# Adafruit_AirLift_FeatherWing.net
KiCad netlist of a schematic drawn in EAGLE
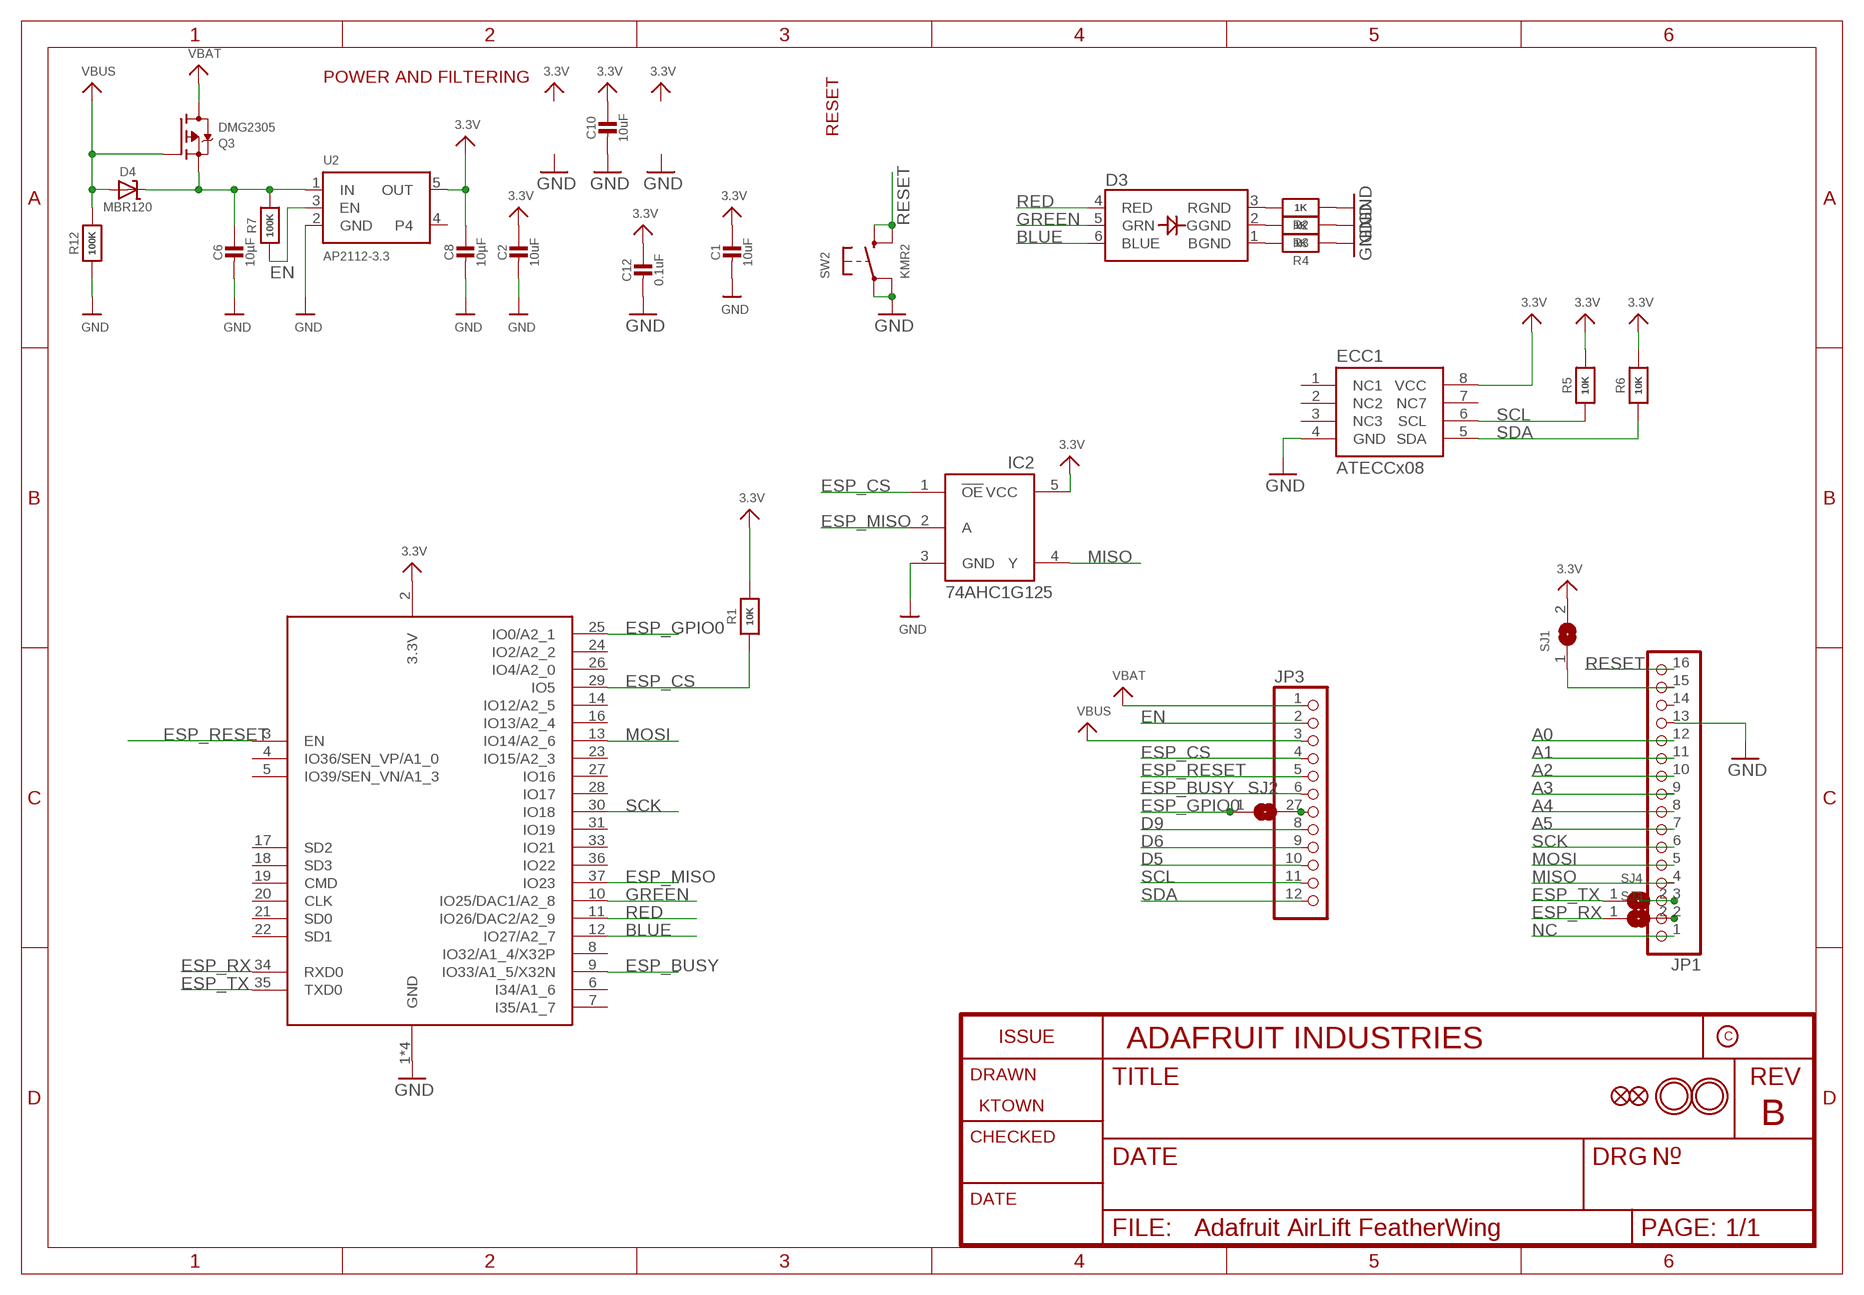
[diagram p0: schematic, sheet 1]

(export (version "E")
  (design (tool "Eeschema 10.0.6"))
  (components
    (comp (ref "C1")
      (value "10uF")
      (footprint "eagle-import:0805-NO")
      (libsource (lib "eagle-import") (part "CAP_CERAMIC0805-NOOUTLINE"))
    )
    (comp (ref "C2")
      (value "10uF")
      (footprint "eagle-import:0805-NO")
      (libsource (lib "eagle-import") (part "CAP_CERAMIC0805-NOOUTLINE"))
    )
    (comp (ref "C6")
      (value "10µF")
      (footprint "eagle-import:0805-NO")
      (libsource (lib "eagle-import") (part "CAP_CERAMIC0805-NOOUTLINE"))
    )
    (comp (ref "C8")
      (value "10µF")
      (footprint "eagle-import:0805-NO")
      (fields (field (name "REV") "B"))
      (libsource (lib "eagle-import") (part "CAP_CERAMIC0805-NOOUTLINE"))
    )
    (comp (ref "C10")
      (value "10uF")
      (footprint "eagle-import:0805-NO")
      (libsource (lib "eagle-import") (part "CAP_CERAMIC0805-NOOUTLINE"))
    )
    (comp (ref "C12")
      (value "0.1uF")
      (footprint "eagle-import:0603-NO")
      (libsource (lib "eagle-import") (part "CAP_CERAMIC0603_NO"))
    )
    (comp (ref "D3")
      (value "LED_RGB_PLCC6CREE-CLV6A")
      (footprint "eagle-import:RGBLED_PLCC6")
      (libsource (lib "eagle-import") (part "LED_RGB_PLCC6CREE-CLV6A"))
    )
    (comp (ref "D4")
      (value "MBR120")
      (footprint "eagle-import:SOD-123")
      (libsource (lib "eagle-import") (part "DIODE-SCHOTTKYSOD-123"))
    )
    (comp (ref "ECC1")
      (value "ATECCx08")
      (footprint "eagle-import:SOIC8")
      (libsource (lib "eagle-import") (part "ATECC108"))
    )
    (comp (ref "IC2")
      (value "74AHC1G125")
      (footprint "eagle-import:SOT23-5L")
      (libsource (lib "eagle-import") (part "74AHC1G125"))
    )
    (comp (ref "JP1")
      (value "HEADER-1X16_MIN")
      (footprint "eagle-import:1X16_ROUND_MIN")
      (libsource (lib "eagle-import") (part "HEADER-1X16_MIN"))
    )
    (comp (ref "JP3")
      (value "HEADER-1X12_MIN")
      (footprint "eagle-import:1X12_ROUND_MIN")
      (libsource (lib "eagle-import") (part "HEADER-1X12_MIN"))
    )
    (comp (ref "Q3")
      (value "DMG2305")
      (footprint "eagle-import:SOT23-R")
      (libsource (lib "eagle-import") (part "MOSFET-P"))
    )
    (comp (ref "R1")
      (value "10K")
      (footprint "eagle-import:0603-NO")
      (libsource (lib "eagle-import") (part "RESISTOR_0603_NOOUT"))
    )
    (comp (ref "R2")
      (value "1K")
      (footprint "eagle-import:0603-NO")
      (libsource (lib "eagle-import") (part "RESISTOR_0603_NOOUT"))
    )
    (comp (ref "R3")
      (value "1K")
      (footprint "eagle-import:0603-NO")
      (libsource (lib "eagle-import") (part "RESISTOR_0603_NOOUT"))
    )
    (comp (ref "R4")
      (value "1K")
      (footprint "eagle-import:0603-NO")
      (libsource (lib "eagle-import") (part "RESISTOR_0603_NOOUT"))
    )
    (comp (ref "R5")
      (value "10K")
      (footprint "eagle-import:0603-NO")
      (libsource (lib "eagle-import") (part "RESISTOR_0603_NOOUT"))
    )
    (comp (ref "R6")
      (value "10K")
      (footprint "eagle-import:0603-NO")
      (libsource (lib "eagle-import") (part "RESISTOR_0603_NOOUT"))
    )
    (comp (ref "R7")
      (value "100K")
      (footprint "eagle-import:0603-NO")
      (libsource (lib "eagle-import") (part "RESISTOR_0603_NOOUT"))
    )
    (comp (ref "R12")
      (value "100K")
      (footprint "eagle-import:0603-NO")
      (libsource (lib "eagle-import") (part "RESISTOR_0603_NOOUT"))
    )
    (comp (ref "SJ1")
      (value "SOLDERJUMPER")
      (footprint "eagle-import:SOLDERJUMPER_ARROW_NOPASTE")
      (libsource (lib "eagle-import") (part "SOLDERJUMPER"))
    )
    (comp (ref "SJ2")
      (value "SOLDERJUMPER")
      (footprint "eagle-import:SOLDERJUMPER_ARROW_NOPASTE")
      (libsource (lib "eagle-import") (part "SOLDERJUMPER"))
    )
    (comp (ref "SJ3")
      (value "SOLDERJUMPER")
      (footprint "eagle-import:SOLDERJUMPER_ARROW_NOPASTE")
      (libsource (lib "eagle-import") (part "SOLDERJUMPER"))
    )
    (comp (ref "SJ4")
      (value "SOLDERJUMPER")
      (footprint "eagle-import:SOLDERJUMPER_ARROW_NOPASTE")
      (libsource (lib "eagle-import") (part "SOLDERJUMPER"))
    )
    (comp (ref "SW2")
      (value "KMR2")
      (footprint "eagle-import:BTN_KMR2_4.6X2.8")
      (libsource (lib "eagle-import") (part "SWITCH_TACT_SMT4.6X2.8"))
    )
    (comp (ref "U$31")
      (value "MOUNTINGHOLE2.5")
      (footprint "eagle-import:MOUNTINGHOLE_2.5_PLATED")
      (libsource (lib "eagle-import") (part "MOUNTINGHOLE2.5"))
    )
    (comp (ref "U$32")
      (value "MOUNTINGHOLE2.5")
      (footprint "eagle-import:MOUNTINGHOLE_2.5_PLATED")
      (libsource (lib "eagle-import") (part "MOUNTINGHOLE2.5"))
    )
    (comp (ref "U$34")
      (value "FIDUCIAL_1MM")
      (footprint "eagle-import:FIDUCIAL_1MM")
      (libsource (lib "eagle-import") (part "FIDUCIAL_1MM"))
    )
    (comp (ref "U$35")
      (value "FIDUCIAL_1MM")
      (footprint "eagle-import:FIDUCIAL_1MM")
      (libsource (lib "eagle-import") (part "FIDUCIAL_1MM"))
    )
    (comp (ref "U2")
      (value "AP2112-3.3")
      (footprint "eagle-import:SOT23-5")
      (libsource (lib "eagle-import") (part "VREG_SOT23-5"))
    )
    (comp (ref "X3")
      (value "ESP32_WROOM32_SKINNY")
      (footprint "eagle-import:WROOM32_SKINNY")
      (libsource (lib "eagle-import") (part "ESP32_WROOM32_SKINNY"))
    )
  )
  (nets
    (net (code "1") (name "/A0") (class "Default")
      (node (ref "JP1") (pin "12") (pinfunction "12_12") (pintype "passive"))
    )
    (net (code "2") (name "/A1") (class "Default")
      (node (ref "JP1") (pin "11") (pinfunction "11_11") (pintype "passive"))
    )
    (net (code "3") (name "/A2") (class "Default")
      (node (ref "JP1") (pin "10") (pinfunction "10_10") (pintype "passive"))
    )
    (net (code "4") (name "/A3") (class "Default")
      (node (ref "JP1") (pin "9") (pinfunction "9_9") (pintype "passive"))
    )
    (net (code "5") (name "/A4") (class "Default")
      (node (ref "JP1") (pin "8") (pinfunction "8_8") (pintype "passive"))
    )
    (net (code "6") (name "/A5") (class "Default")
      (node (ref "JP1") (pin "7") (pinfunction "7_7") (pintype "passive"))
    )
    (net (code "7") (name "/BLUE") (class "Default")
      (node (ref "D3") (pin "6") (pinfunction "BLUE_6") (pintype "bidirectional"))
      (node (ref "X3") (pin "12") (pinfunction "IO27/A2_7_12") (pintype "bidirectional"))
    )
    (net (code "8") (name "/D5") (class "Default")
      (node (ref "JP3") (pin "10") (pinfunction "10_10") (pintype "passive"))
    )
    (net (code "9") (name "/D6") (class "Default")
      (node (ref "JP3") (pin "9") (pinfunction "9_9") (pintype "passive"))
    )
    (net (code "10") (name "/D9") (class "Default")
      (node (ref "JP3") (pin "8") (pinfunction "8_8") (pintype "passive"))
    )
    (net (code "11") (name "/EN") (class "Default")
      (node (ref "JP3") (pin "2") (pinfunction "2_2") (pintype "passive"))
      (node (ref "R7") (pin "1") (pinfunction "1_1") (pintype "passive"))
      (node (ref "U2") (pin "3") (pinfunction "EN_3") (pintype "input"))
    )
    (net (code "12") (name "/ESP_BUSY") (class "Default")
      (node (ref "JP3") (pin "6") (pinfunction "6_6") (pintype "passive"))
      (node (ref "X3") (pin "9") (pinfunction "IO33/A1_5/X32N_9") (pintype "bidirectional"))
    )
    (net (code "13") (name "/ESP_CS") (class "Default")
      (node (ref "IC2") (pin "1") (pinfunction "~{OE}_1") (pintype "input"))
      (node (ref "JP3") (pin "4") (pinfunction "4_4") (pintype "passive"))
      (node (ref "R1") (pin "1") (pinfunction "1_1") (pintype "passive"))
      (node (ref "X3") (pin "29") (pinfunction "IO5_29") (pintype "bidirectional"))
    )
    (net (code "14") (name "/ESP_GPIO0") (class "Default")
      (node (ref "SJ2") (pin "1") (pinfunction "1_1") (pintype "passive"))
      (node (ref "X3") (pin "25") (pinfunction "IO0/A2_1_25") (pintype "bidirectional"))
    )
    (net (code "15") (name "/ESP_MISO") (class "Default")
      (node (ref "IC2") (pin "2") (pinfunction "A_2") (pintype "input"))
      (node (ref "X3") (pin "37") (pinfunction "IO23_37") (pintype "bidirectional"))
    )
    (net (code "16") (name "/ESP_RESET") (class "Default")
      (node (ref "JP3") (pin "5") (pinfunction "5_5") (pintype "passive"))
      (node (ref "X3") (pin "3") (pinfunction "EN_3") (pintype "input"))
    )
    (net (code "17") (name "/ESP_RX") (class "Default")
      (node (ref "SJ3") (pin "1") (pinfunction "1_1") (pintype "passive"))
      (node (ref "X3") (pin "34") (pinfunction "RXD0_34") (pintype "input"))
    )
    (net (code "18") (name "/ESP_TX") (class "Default")
      (node (ref "SJ4") (pin "1") (pinfunction "1_1") (pintype "passive"))
      (node (ref "X3") (pin "35") (pinfunction "TXD0_35") (pintype "output"))
    )
    (net (code "19") (name "/GREEN") (class "Default")
      (node (ref "D3") (pin "5") (pinfunction "GRN_5") (pintype "bidirectional"))
      (node (ref "X3") (pin "10") (pinfunction "IO25/DAC1/A2_8_10") (pintype "bidirectional"))
    )
    (net (code "20") (name "/MISO") (class "Default")
      (node (ref "IC2") (pin "4") (pinfunction "Y_4") (pintype "output"))
      (node (ref "JP1") (pin "4") (pinfunction "4_4") (pintype "passive"))
    )
    (net (code "21") (name "/MOSI") (class "Default")
      (node (ref "JP1") (pin "5") (pinfunction "5_5") (pintype "passive"))
      (node (ref "X3") (pin "13") (pinfunction "IO14/A2_6_13") (pintype "bidirectional"))
    )
    (net (code "22") (name "/NC") (class "Default")
      (node (ref "JP1") (pin "1") (pinfunction "1_1") (pintype "passive"))
    )
    (net (code "23") (name "/RED") (class "Default")
      (node (ref "D3") (pin "4") (pinfunction "RED_4") (pintype "bidirectional"))
      (node (ref "X3") (pin "11") (pinfunction "IO26/DAC2/A2_9_11") (pintype "bidirectional"))
    )
    (net (code "24") (name "/RESET") (class "Default")
      (node (ref "JP1") (pin "16") (pinfunction "16_16") (pintype "passive"))
      (node (ref "SW2") (pin "B") (pinfunction "S_B") (pintype "passive"))
      (node (ref "SW2") (pin "B'") (pinfunction "S1_B'") (pintype "passive"))
    )
    (net (code "25") (name "/SCK") (class "Default")
      (node (ref "JP1") (pin "6") (pinfunction "6_6") (pintype "passive"))
      (node (ref "X3") (pin "30") (pinfunction "IO18_30") (pintype "bidirectional"))
    )
    (net (code "26") (name "/SCL") (class "Default")
      (node (ref "ECC1") (pin "6") (pinfunction "SCL_6") (pintype "bidirectional"))
      (node (ref "JP3") (pin "11") (pinfunction "11_11") (pintype "passive"))
      (node (ref "R5") (pin "1") (pinfunction "1_1") (pintype "passive"))
    )
    (net (code "27") (name "/SDA") (class "Default")
      (node (ref "ECC1") (pin "5") (pinfunction "SDA_5") (pintype "bidirectional"))
      (node (ref "JP3") (pin "12") (pinfunction "12_12") (pintype "passive"))
      (node (ref "R6") (pin "1") (pinfunction "1_1") (pintype "passive"))
    )
    (net (code "28") (name "3.3V") (class "Default")
      (node (ref "C1") (pin "1") (pinfunction "1_1") (pintype "passive"))
      (node (ref "C10") (pin "1") (pinfunction "1_1") (pintype "passive"))
      (node (ref "C12") (pin "1") (pinfunction "1_1") (pintype "passive"))
      (node (ref "C2") (pin "1") (pinfunction "1_1") (pintype "passive"))
      (node (ref "C8") (pin "1") (pinfunction "1_1") (pintype "passive"))
      (node (ref "ECC1") (pin "8") (pinfunction "VCC_8") (pintype "power_in"))
      (node (ref "IC2") (pin "5") (pinfunction "VCC_5") (pintype "power_in"))
      (node (ref "R1") (pin "2") (pinfunction "2_2") (pintype "passive"))
      (node (ref "R5") (pin "2") (pinfunction "2_2") (pintype "passive"))
      (node (ref "R6") (pin "2") (pinfunction "2_2") (pintype "passive"))
      (node (ref "SJ1") (pin "2") (pinfunction "2_2") (pintype "passive"))
      (node (ref "U2") (pin "5") (pinfunction "OUT_5") (pintype "power_in"))
      (node (ref "X3") (pin "2") (pinfunction "3.3V_2") (pintype "passive"))
    )
    (net (code "29") (name "GND") (class "Default")
      (node (ref "C1") (pin "2") (pinfunction "2_2") (pintype "passive"))
      (node (ref "C10") (pin "2") (pinfunction "2_2") (pintype "passive"))
      (node (ref "C12") (pin "2") (pinfunction "2_2") (pintype "passive"))
      (node (ref "C2") (pin "2") (pinfunction "2_2") (pintype "passive"))
      (node (ref "C6") (pin "2") (pinfunction "2_2") (pintype "passive"))
      (node (ref "C8") (pin "2") (pinfunction "2_2") (pintype "passive"))
      (node (ref "ECC1") (pin "4") (pinfunction "GND_4") (pintype "power_in"))
      (node (ref "IC2") (pin "3") (pinfunction "GND_3") (pintype "power_in"))
      (node (ref "JP1") (pin "13") (pinfunction "13_13") (pintype "passive"))
      (node (ref "R12") (pin "1") (pinfunction "1_1") (pintype "passive"))
      (node (ref "R2") (pin "1") (pinfunction "1_1") (pintype "passive"))
      (node (ref "R3") (pin "1") (pinfunction "1_1") (pintype "passive"))
      (node (ref "R4") (pin "1") (pinfunction "1_1") (pintype "passive"))
      (node (ref "SW2") (pin "A") (pinfunction "P_A") (pintype "passive"))
      (node (ref "SW2") (pin "A'") (pinfunction "P1_A'") (pintype "passive"))
      (node (ref "U2") (pin "2") (pinfunction "GND_2") (pintype "power_in"))
      (node (ref "X3") (pin "1") (pinfunction "GND_1") (pintype "passive"))
      (node (ref "X3") (pin "15") (pinfunction "GND_15") (pintype "passive"))
      (node (ref "X3") (pin "38") (pinfunction "GND_38") (pintype "passive"))
      (node (ref "X3") (pin "P$1") (pinfunction "GND_P$1") (pintype "passive"))
    )
    (net (code "30") (name "Net-(D3-BGND)") (class "Default")
      (node (ref "D3") (pin "1") (pinfunction "BGND_1") (pintype "power_in"))
      (node (ref "R4") (pin "2") (pinfunction "2_2") (pintype "passive"))
    )
    (net (code "31") (name "Net-(D3-GGND)") (class "Default")
      (node (ref "D3") (pin "2") (pinfunction "GGND_2") (pintype "power_in"))
      (node (ref "R3") (pin "2") (pinfunction "2_2") (pintype "passive"))
    )
    (net (code "32") (name "Net-(D3-RGND)") (class "Default")
      (node (ref "D3") (pin "3") (pinfunction "RGND_3") (pintype "power_in"))
      (node (ref "R2") (pin "2") (pinfunction "2_2") (pintype "passive"))
    )
    (net (code "33") (name "Net-(JP1-Pad2)") (class "Default")
      (node (ref "JP1") (pin "2") (pinfunction "2_2") (pintype "passive"))
      (node (ref "SJ3") (pin "2") (pinfunction "2_2") (pintype "passive"))
    )
    (net (code "34") (name "Net-(JP1-Pad3)") (class "Default")
      (node (ref "JP1") (pin "3") (pinfunction "3_3") (pintype "passive"))
      (node (ref "SJ4") (pin "2") (pinfunction "2_2") (pintype "passive"))
    )
    (net (code "35") (name "Net-(JP1-Pad15)") (class "Default")
      (node (ref "JP1") (pin "15") (pinfunction "15_15") (pintype "passive"))
      (node (ref "SJ1") (pin "1") (pinfunction "1_1") (pintype "passive"))
    )
    (net (code "36") (name "Net-(JP3-Pad7)") (class "Default")
      (node (ref "JP3") (pin "7") (pinfunction "7_7") (pintype "passive"))
      (node (ref "SJ2") (pin "2") (pinfunction "2_2") (pintype "passive"))
    )
    (net (code "37") (name "Net-(Q3-S)") (class "Default")
      (node (ref "C6") (pin "1") (pinfunction "1_1") (pintype "passive"))
      (node (ref "D4") (pin "C") (pinfunction "C_C") (pintype "passive"))
      (node (ref "Q3") (pin "2") (pinfunction "S_2") (pintype "passive"))
      (node (ref "R7") (pin "2") (pinfunction "2_2") (pintype "passive"))
      (node (ref "U2") (pin "1") (pinfunction "IN_1") (pintype "power_in"))
    )
    (net (code "38") (name "VBAT") (class "Default")
      (node (ref "JP3") (pin "1") (pinfunction "1_1") (pintype "passive"))
      (node (ref "Q3") (pin "3") (pinfunction "D_3") (pintype "passive"))
    )
    (net (code "39") (name "VBUS") (class "Default")
      (node (ref "D4") (pin "A") (pinfunction "A_A") (pintype "passive"))
      (node (ref "JP3") (pin "3") (pinfunction "3_3") (pintype "passive"))
      (node (ref "Q3") (pin "1") (pinfunction "G_1") (pintype "passive"))
      (node (ref "R12") (pin "2") (pinfunction "2_2") (pintype "passive"))
    )
    (net (code "40") (name "unconnected-(ECC1-NC1-Pad1)") (class "Default")
      (node (ref "ECC1") (pin "1") (pinfunction "NC1_1") (pintype "bidirectional"))
    )
    (net (code "41") (name "unconnected-(ECC1-NC2-Pad2)") (class "Default")
      (node (ref "ECC1") (pin "2") (pinfunction "NC2_2") (pintype "no_connect"))
    )
    (net (code "42") (name "unconnected-(ECC1-NC3-Pad3)") (class "Default")
      (node (ref "ECC1") (pin "3") (pinfunction "NC3_3") (pintype "no_connect"))
    )
    (net (code "43") (name "unconnected-(ECC1-NC7-Pad7)") (class "Default")
      (node (ref "ECC1") (pin "7") (pinfunction "NC7_7") (pintype "no_connect"))
    )
    (net (code "44") (name "unconnected-(JP1-Pad14)") (class "Default")
      (node (ref "JP1") (pin "14") (pinfunction "14_14") (pintype "passive"))
    )
    (net (code "45") (name "unconnected-(U2-P4-Pad4)") (class "Default")
      (node (ref "U2") (pin "4") (pinfunction "P4_4") (pintype "bidirectional"))
    )
    (net (code "46") (name "unconnected-(X3-CLK-Pad20)") (class "Default")
      (node (ref "X3") (pin "20") (pinfunction "CLK_20") (pintype "bidirectional"))
    )
    (net (code "47") (name "unconnected-(X3-CMD-Pad19)") (class "Default")
      (node (ref "X3") (pin "19") (pinfunction "CMD_19") (pintype "bidirectional"))
    )
    (net (code "48") (name "unconnected-(X3-I34{slash}A1_6-Pad6)") (class "Default")
      (node (ref "X3") (pin "6") (pinfunction "I34/A1_6_6") (pintype "bidirectional"))
    )
    (net (code "49") (name "unconnected-(X3-I35{slash}A1_7-Pad7)") (class "Default")
      (node (ref "X3") (pin "7") (pinfunction "I35/A1_7_7") (pintype "bidirectional"))
    )
    (net (code "50") (name "unconnected-(X3-IO2{slash}A2_2-Pad24)") (class "Default")
      (node (ref "X3") (pin "24") (pinfunction "IO2/A2_2_24") (pintype "bidirectional"))
    )
    (net (code "51") (name "unconnected-(X3-IO4{slash}A2_0-Pad26)") (class "Default")
      (node (ref "X3") (pin "26") (pinfunction "IO4/A2_0_26") (pintype "bidirectional"))
    )
    (net (code "52") (name "unconnected-(X3-IO12{slash}A2_5-Pad14)") (class "Default")
      (node (ref "X3") (pin "14") (pinfunction "IO12/A2_5_14") (pintype "bidirectional"))
    )
    (net (code "53") (name "unconnected-(X3-IO13{slash}A2_4-Pad16)") (class "Default")
      (node (ref "X3") (pin "16") (pinfunction "IO13/A2_4_16") (pintype "bidirectional"))
    )
    (net (code "54") (name "unconnected-(X3-IO15{slash}A2_3-Pad23)") (class "Default")
      (node (ref "X3") (pin "23") (pinfunction "IO15/A2_3_23") (pintype "bidirectional"))
    )
    (net (code "55") (name "unconnected-(X3-IO16-Pad27)") (class "Default")
      (node (ref "X3") (pin "27") (pinfunction "IO16_27") (pintype "bidirectional"))
    )
    (net (code "56") (name "unconnected-(X3-IO17-Pad28)") (class "Default")
      (node (ref "X3") (pin "28") (pinfunction "IO17_28") (pintype "bidirectional"))
    )
    (net (code "57") (name "unconnected-(X3-IO19-Pad31)") (class "Default")
      (node (ref "X3") (pin "31") (pinfunction "IO19_31") (pintype "bidirectional"))
    )
    (net (code "58") (name "unconnected-(X3-IO21-Pad33)") (class "Default")
      (node (ref "X3") (pin "33") (pinfunction "IO21_33") (pintype "bidirectional"))
    )
    (net (code "59") (name "unconnected-(X3-IO22-Pad36)") (class "Default")
      (node (ref "X3") (pin "36") (pinfunction "IO22_36") (pintype "bidirectional"))
    )
    (net (code "60") (name "unconnected-(X3-IO32{slash}A1_4{slash}X32P-Pad8)") (class "Default")
      (node (ref "X3") (pin "8") (pinfunction "IO32/A1_4/X32P_8") (pintype "bidirectional"))
    )
    (net (code "61") (name "unconnected-(X3-IO36{slash}SEN_VP{slash}A1_0-Pad4)") (class "Default")
      (node (ref "X3") (pin "4") (pinfunction "IO36/SEN_VP/A1_0_4") (pintype "passive"))
    )
    (net (code "62") (name "unconnected-(X3-IO39{slash}SEN_VN{slash}A1_3-Pad5)") (class "Default")
      (node (ref "X3") (pin "5") (pinfunction "IO39/SEN_VN/A1_3_5") (pintype "passive"))
    )
    (net (code "63") (name "unconnected-(X3-SD0-Pad21)") (class "Default")
      (node (ref "X3") (pin "21") (pinfunction "SD0_21") (pintype "bidirectional"))
    )
    (net (code "64") (name "unconnected-(X3-SD1-Pad22)") (class "Default")
      (node (ref "X3") (pin "22") (pinfunction "SD1_22") (pintype "bidirectional"))
    )
    (net (code "65") (name "unconnected-(X3-SD2-Pad17)") (class "Default")
      (node (ref "X3") (pin "17") (pinfunction "SD2_17") (pintype "bidirectional"))
    )
    (net (code "66") (name "unconnected-(X3-SD3-Pad18)") (class "Default")
      (node (ref "X3") (pin "18") (pinfunction "SD3_18") (pintype "bidirectional"))
    )
  )
)
